# nrf21540_qdaa_var1.net
KiCad netlist of a schematic drawn in Altium Designer
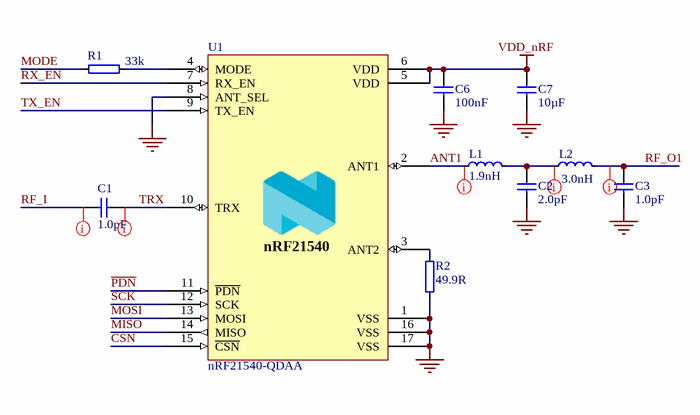
[diagram p0: nrf21540_qdaa_var1.SchDoc]

(export (version "E")
  (design (tool "Eeschema 10.0.6"))
  (components
    (comp (ref "C1")
      (value "1.0pF")
      (footprint "CAPC0603X03L_C")
      (description "Capacitor, NP0, ±0.05pF, 50V")
      (fields (field (name "PART NUMBER") "C0201-1.0p") (field (name "AUTHOR") "rsk"))
      (libsource (lib "AltiumLib") (part "CAP"))
    )
    (comp (ref "C2")
      (value "2.0pF")
      (footprint "CAPC0603X03L_C")
      (description "Capacitor, NP0, ±0.05pF, 25V")
      (fields (field (name "PART NUMBER") "C0201-2.0p-HQ-Murata") (field (name "AUTHOR") "rsk"))
      (libsource (lib "AltiumLib") (part "CAP"))
    )
    (comp (ref "C3")
      (value "1.0pF")
      (footprint "CAPC0603X03L_C")
      (description "Capacitor, NP0, ±0.05pF, 50V")
      (fields (field (name "PART NUMBER") "C0201-1.0p") (field (name "AUTHOR") "rsk"))
      (libsource (lib "AltiumLib") (part "CAP"))
    )
    (comp (ref "C6")
      (value "100nF")
      (footprint "CAPC0603X03L_C")
      (description "Capacitor, X5R, ±10%")
      (fields (field (name "PART NUMBER") "C0201-100n") (field (name "AUTHOR") "rsk"))
      (libsource (lib "AltiumLib") (part "CAP"))
    )
    (comp (ref "C7")
      (value "10µF")
      (footprint "CAPC1608X06L")
      (description "Capacitor, X5R, ±20%")
      (fields (field (name "PART NUMBER") "C0603-10µ") (field (name "AUTHOR") "rsk"))
      (libsource (lib "AltiumLib") (part "CAP"))
    )
    (comp (ref "L1")
      (value "1.9nH")
      (footprint "INDC0603X03L_C")
      (description "Inductor, 600mA, ±0.1ｎH, 120mOhm")
      (fields (field (name "PART NUMBER") "L0201-1n9-HQ-Murata") (field (name "AUTHOR") "rsk"))
      (libsource (lib "AltiumLib") (part "IND"))
    )
    (comp (ref "L2")
      (value "3.0nH")
      (footprint "INDC0603X03L_C")
      (description "Inductor, 600mA, ±0.1ｎH, 120mOhm")
      (fields (field (name "PART NUMBER") "L0201-3n0-HQ-Murata") (field (name "AUTHOR") "rsk"))
      (libsource (lib "AltiumLib") (part "IND"))
    )
    (comp (ref "R1")
      (value "33k")
      (footprint "RESC0603X03L_C")
      (description "Resistor, ±1%, 0.05W")
      (fields (field (name "PART NUMBER") "R0201-33k") (field (name "AUTHOR") "rsk"))
      (libsource (lib "AltiumLib") (part "RES"))
    )
    (comp (ref "R2")
      (value "49.9R")
      (footprint "RESC0603X03L_C")
      (description "Resistor, ±1%, 0.05W")
      (fields (field (name "PART NUMBER") "R0201-49R9") (field (name "AUTHOR") "getr"))
      (libsource (lib "AltiumLib") (part "RES"))
    )
    (comp (ref "U1")
      (value "nRF21540-QDAA")
      (footprint "QFN65P400X400X65_HS-17N")
      (description "Radio front-end / range extender for 2.4GHz")
      (fields (field (name "AUTHOR") "rsk"))
      (libsource (lib "AltiumLib") (part "nRF21540-QDAA"))
    )
  )
  (nets
    (net (code "1") (name "/ANT1") (class "Default")
      (node (ref "L1") (pin "1") (pinfunction "1_1") (pintype "passive"))
      (node (ref "U1") (pin "2") (pinfunction "ANT1_2") (pintype "bidirectional"))
    )
    (net (code "2") (name "/MISO") (class "Default")
      (node (ref "U1") (pin "14") (pinfunction "MISO_14") (pintype "output"))
    )
    (net (code "3") (name "/MODE") (class "Default")
      (node (ref "R1") (pin "1") (pinfunction "1_1") (pintype "passive"))
    )
    (net (code "4") (name "/MOSI") (class "Default")
      (node (ref "U1") (pin "13") (pinfunction "MOSI_13") (pintype "input"))
    )
    (net (code "5") (name "/RF_I") (class "Default")
      (node (ref "C1") (pin "1") (pinfunction "1_1") (pintype "passive"))
    )
    (net (code "6") (name "/RF_O1") (class "Default")
      (node (ref "C3") (pin "2") (pinfunction "2_2") (pintype "passive"))
      (node (ref "L2") (pin "2") (pinfunction "2_2") (pintype "passive"))
    )
    (net (code "7") (name "/RX_EN") (class "Default")
      (node (ref "U1") (pin "7") (pinfunction "RX_EN_7") (pintype "input"))
    )
    (net (code "8") (name "/SCK") (class "Default")
      (node (ref "U1") (pin "12") (pinfunction "SCK_12") (pintype "input"))
    )
    (net (code "9") (name "/TRX") (class "Default")
      (node (ref "C1") (pin "2") (pinfunction "2_2") (pintype "passive"))
      (node (ref "U1") (pin "10") (pinfunction "TRX_10") (pintype "bidirectional"))
    )
    (net (code "10") (name "/TX_EN") (class "Default")
      (node (ref "U1") (pin "9") (pinfunction "TX_EN_9") (pintype "input"))
    )
    (net (code "11") (name "/~{CSN}") (class "Default")
      (node (ref "U1") (pin "15") (pinfunction "~{CSN}_15") (pintype "input"))
    )
    (net (code "12") (name "/~{PDN}") (class "Default")
      (node (ref "U1") (pin "11") (pinfunction "~{PDN}_11") (pintype "input"))
    )
    (net (code "13") (name "GND") (class "Default")
      (node (ref "C2") (pin "1") (pinfunction "1_1") (pintype "passive"))
      (node (ref "C3") (pin "1") (pinfunction "1_1") (pintype "passive"))
      (node (ref "C6") (pin "1") (pinfunction "1_1") (pintype "passive"))
      (node (ref "C7") (pin "1") (pinfunction "1_1") (pintype "passive"))
      (node (ref "R2") (pin "2") (pinfunction "2_2") (pintype "passive"))
      (node (ref "U1") (pin "1") (pinfunction "VSS_1") (pintype "power_in"))
      (node (ref "U1") (pin "16") (pinfunction "VSS_16") (pintype "power_in"))
      (node (ref "U1") (pin "17") (pinfunction "VSS_17") (pintype "power_in"))
      (node (ref "U1") (pin "8") (pinfunction "ANT_SEL_8") (pintype "input"))
    )
    (net (code "14") (name "Net-(C2-Pad2)") (class "Default")
      (node (ref "C2") (pin "2") (pinfunction "2_2") (pintype "passive"))
      (node (ref "L1") (pin "2") (pinfunction "2_2") (pintype "passive"))
      (node (ref "L2") (pin "1") (pinfunction "1_1") (pintype "passive"))
    )
    (net (code "15") (name "Net-(U1-ANT2)") (class "Default")
      (node (ref "R2") (pin "1") (pinfunction "1_1") (pintype "passive"))
      (node (ref "U1") (pin "3") (pinfunction "ANT2_3") (pintype "bidirectional"))
    )
    (net (code "16") (name "Net-(U1-MODE)") (class "Default")
      (node (ref "R1") (pin "2") (pinfunction "2_2") (pintype "passive"))
      (node (ref "U1") (pin "4") (pinfunction "MODE_4") (pintype "bidirectional"))
    )
    (net (code "17") (name "VDD_nRF") (class "Default")
      (node (ref "C6") (pin "2") (pinfunction "2_2") (pintype "passive"))
      (node (ref "C7") (pin "2") (pinfunction "2_2") (pintype "passive"))
      (node (ref "U1") (pin "5") (pinfunction "VDD_5") (pintype "power_in"))
      (node (ref "U1") (pin "6") (pinfunction "VDD_6") (pintype "power_in"))
    )
  )
)
